# BazzFussNoBypass.net
KiCad netlist of a schematic drawn in EAGLE
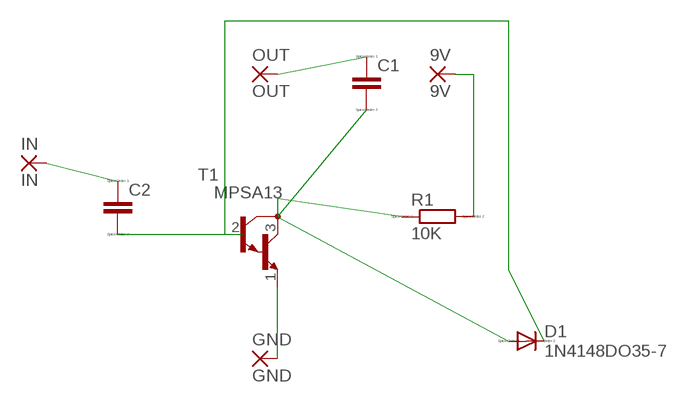
[diagram p0: schematic, sheet 1]

(export (version "E")
  (design (tool "Eeschema 10.0.6"))
  (components
    (comp (ref "9V")
      (value "9V")
      (footprint "eagle-import:1,6_0,8")
      (libsource (lib "eagle-import") (part "1,6/0,8"))
    )
    (comp (ref "C1")
      (value "C-EU025-025X050")
      (footprint "eagle-import:C025-025X050")
      (libsource (lib "eagle-import") (part "C-EU025-025X050"))
    )
    (comp (ref "C2")
      (value "C-EU025-025X050")
      (footprint "eagle-import:C025-025X050")
      (libsource (lib "eagle-import") (part "C-EU025-025X050"))
    )
    (comp (ref "D1")
      (value "1N4148DO35-7")
      (footprint "eagle-import:DO35-7")
      (libsource (lib "eagle-import") (part "1N4148DO35-7"))
    )
    (comp (ref "GND")
      (value "GND")
      (footprint "eagle-import:1,6_0,8")
      (libsource (lib "eagle-import") (part "1,6/0,8"))
    )
    (comp (ref "IN")
      (value "IN")
      (footprint "eagle-import:1,6_0,8")
      (libsource (lib "eagle-import") (part "1,6/0,8"))
    )
    (comp (ref "OUT")
      (value "OUT")
      (footprint "eagle-import:1,6_0,8")
      (libsource (lib "eagle-import") (part "1,6/0,8"))
    )
    (comp (ref "R1")
      (value "10K")
      (footprint "eagle-import:0207_10")
      (libsource (lib "eagle-import") (part "R0207/10"))
    )
    (comp (ref "T1")
      (value "MPSA13")
      (footprint "eagle-import:TO92")
      (libsource (lib "eagle-import") (part "BC517"))
    )
  )
  (nets
    (net (code "1") (name "Net-(9V-P)") (class "Default")
      (node (ref "9V") (pin "1") (pinfunction "P_1") (pintype "passive"))
      (node (ref "R1") (pin "2") (pinfunction "2_2") (pintype "passive"))
    )
    (net (code "2") (name "Net-(GND-P)") (class "Default")
      (node (ref "GND") (pin "1") (pinfunction "P_1") (pintype "passive"))
      (node (ref "T1") (pin "1") (pinfunction "E_1") (pintype "passive"))
    )
    (net (code "3") (name "Net-(IN-P)") (class "Default")
      (node (ref "C2") (pin "1") (pinfunction "1_1") (pintype "passive"))
      (node (ref "IN") (pin "1") (pinfunction "P_1") (pintype "passive"))
    )
    (net (code "4") (name "Net-(OUT-P)") (class "Default")
      (node (ref "C1") (pin "1") (pinfunction "1_1") (pintype "passive"))
      (node (ref "OUT") (pin "1") (pinfunction "P_1") (pintype "passive"))
    )
    (net (code "5") (name "Net-(T1-B)") (class "Default")
      (node (ref "C2") (pin "2") (pinfunction "2_2") (pintype "passive"))
      (node (ref "D1") (pin "C") (pinfunction "C_C") (pintype "passive"))
      (node (ref "T1") (pin "2") (pinfunction "B_2") (pintype "passive"))
    )
    (net (code "6") (name "Net-(T1-C)") (class "Default")
      (node (ref "C1") (pin "2") (pinfunction "2_2") (pintype "passive"))
      (node (ref "D1") (pin "A") (pinfunction "A_A") (pintype "passive"))
      (node (ref "R1") (pin "1") (pinfunction "1_1") (pintype "passive"))
      (node (ref "T1") (pin "3") (pinfunction "C_3") (pintype "passive"))
    )
  )
)
